# ESP32_WiFi.net
KiCad netlist of a schematic drawn in Altium Designer
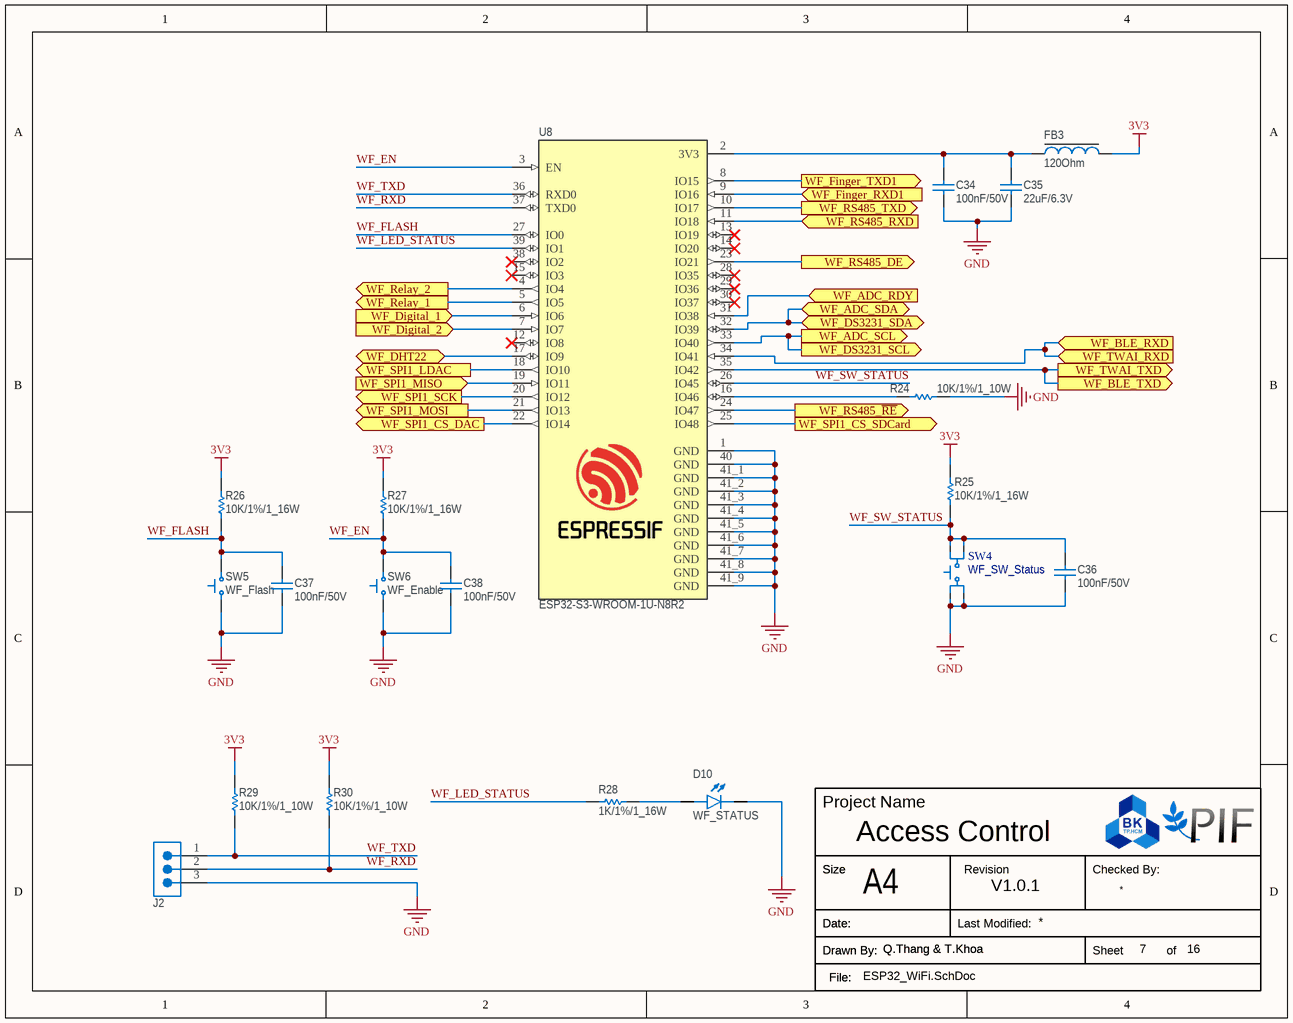
[diagram p0: ESP32_WiFi.SchDoc]

(export (version "E")
  (design (tool "Eeschema 10.0.6"))
  (components
    (comp (ref "C34")
      (value "100nF/50V")
      (footprint "CAP_0805")
      (description "CAP, size 0805, 100nF, 50V")
      (fields (field (name "SUPPLY PART NUMBER") "Tụ Gốm 0805 100nF (0.1uF) 50V"))
      (libsource (lib "BluetoothTracking") (part "Ceramic_Cap_100nF_50V_0805"))
    )
    (comp (ref "C35")
      (value "22uF/6.3V")
      (footprint "CAP_0805")
      (description "CAP, size 0805, 22uF, 6.3V")
      (fields (field (name "SUPPLY PART NUMBER") "Tụ Gốm 0805 22uF 6.3V"))
      (libsource (lib "BluetoothTracking") (part "Ceramic_Cap_22uF_6.3V_0805"))
    )
    (comp (ref "C36")
      (value "100nF/50V")
      (footprint "CAP_0402")
      (description "CAP, size 0402, 100nF, 50V")
      (fields (field (name "SUPPLY PART NUMBER") "Tụ Gốm 0402 100nF (0.1uF) 50V"))
      (libsource (lib "BluetoothTracking") (part "Ceramic_Cap_100nF_50V_0402"))
    )
    (comp (ref "C37")
      (value "100nF/50V")
      (footprint "CAP_0402")
      (description "CAP, size 0402, 100nF, 50V")
      (fields (field (name "SUPPLY PART NUMBER") "Tụ Gốm 0402 100nF (0.1uF) 50V"))
      (libsource (lib "BluetoothTracking") (part "Ceramic_Cap_100nF_50V_0402"))
    )
    (comp (ref "C38")
      (value "100nF/50V")
      (footprint "CAP_0402")
      (description "CAP, size 0402, 100nF, 50V")
      (fields (field (name "SUPPLY PART NUMBER") "Tụ Gốm 0402 100nF (0.1uF) 50V"))
      (libsource (lib "BluetoothTracking") (part "Ceramic_Cap_100nF_50V_0402"))
    )
    (comp (ref "D10")
      (value "WF_STATUS")
      (footprint "LED_0603Y")
      (description "LED Yellow 0603")
      (fields (field (name "SUPPLY PART NUMBER") "LED Vàng 0603 Dán SMD Trong Suốt Harvatek"))
      (libsource (lib "BluetoothTracking") (part "LED_Yellow_0603"))
    )
    (comp (ref "FB3")
      (value "120Ohm")
      (footprint "Ferrite_Bead_0805")
      (description "Ferrite Bead, size 0805, 120Ohm, 2A")
      (fields (field (name "SUPPLY PART NUMBER") "CBW201209U121T Ferrite Beads 2A 120 Ohm 0805"))
      (libsource (lib "BluetoothTracking") (part "Ferrite_Bead_120Ohm_2A_0805"))
    )
    (comp (ref "J2")
      (value "2.54mm_2P")
      (footprint "Header_2.54mm_3P")
      (description "Hàng Rào Đực Đơn 2.54mm 40 Chân 1 Hàng Cao 11.2mm Xuyên Lỗ")
      (libsource (lib "BluetoothTracking") (part "Header_2.54mm_3P"))
    )
    (comp (ref "R24")
      (value "10K/1%/1_10W")
      (footprint "Resistor_0603")
      (description "Resistor 0603 10KOhm 1% 1_10W")
      (fields (field (name "SUPPLY PART NUMBER") "Điện Trở 10 KOhm 0603 1%"))
      (libsource (lib "BluetoothTracking") (part "Res_10K_0603_1%"))
    )
    (comp (ref "R25")
      (value "10K/1%/1_16W")
      (footprint "RESISTOR_0402")
      (description "Resistor 0402 10KOhm 1% 1_16W")
      (fields (field (name "SUPPLY PART NUMBER") "Điện Trở 10 KOhm 0402 1%"))
      (libsource (lib "BluetoothTracking") (part "Res_10K_0402_1%"))
    )
    (comp (ref "R26")
      (value "10K/1%/1_16W")
      (footprint "RESISTOR_0402")
      (description "Resistor 0402 10KOhm 1% 1_16W")
      (fields (field (name "SUPPLY PART NUMBER") "Điện Trở 10 KOhm 0402 1%"))
      (libsource (lib "BluetoothTracking") (part "Res_10K_0402_1%"))
    )
    (comp (ref "R27")
      (value "10K/1%/1_16W")
      (footprint "RESISTOR_0402")
      (description "Resistor 0402 10KOhm 1% 1_16W")
      (fields (field (name "SUPPLY PART NUMBER") "Điện Trở 10 KOhm 0402 1%"))
      (libsource (lib "BluetoothTracking") (part "Res_10K_0402_1%"))
    )
    (comp (ref "R28")
      (value "1K/1%/1_16W")
      (footprint "RESISTOR_0402")
      (description "Resistor 0402 1KOhm 1% 1_16W")
      (fields (field (name "SUPPLY PART NUMBER") "Điện Trở 1 KOhm 0402 1%"))
      (libsource (lib "BluetoothTracking") (part "Res_1K_0402_1%"))
    )
    (comp (ref "R29")
      (value "10K/1%/1_10W")
      (footprint "Resistor_0603")
      (description "Resistor 0603 10KOhm 1% 1_10W")
      (fields (field (name "SUPPLY PART NUMBER") "Điện Trở 10 KOhm 0603 1%"))
      (libsource (lib "BluetoothTracking") (part "Res_10K_0603_1%"))
    )
    (comp (ref "R30")
      (value "10K/1%/1_10W")
      (footprint "Resistor_0603")
      (description "Resistor 0603 10KOhm 1% 1_10W")
      (fields (field (name "SUPPLY PART NUMBER") "Điện Trở 10 KOhm 0603 1%"))
      (libsource (lib "BluetoothTracking") (part "Res_10K_0603_1%"))
    )
    (comp (ref "SW4")
      (value "WF_SW_Status")
      (footprint "Button_4.5x4.7mm_SMD_4P")
      (fields (field (name "SUPPLY PART NUMBER") "Nút Nhấn Rùa 4.5x4.7mm Cao 1.65mm 4 Chân SMD"))
      (libsource (lib "BluetoothTracking") (part "Button_SMD_4.5x4.7mm_4P"))
    )
    (comp (ref "SW5")
      (value "WF_Flash")
      (footprint "Button_3x4mm_SMD_2P")
      (fields (field (name "SUPPLY PART NUMBER") "Nút Nhấn 3x4mm Cao 2.5mm 2 Chân SMD"))
      (libsource (lib "BluetoothTracking") (part "Button_SMD_3x4mm_2P"))
    )
    (comp (ref "SW6")
      (value "WF_Enable")
      (footprint "Button_3x4mm_SMD_2P")
      (fields (field (name "SUPPLY PART NUMBER") "Nút Nhấn 3x4mm Cao 2.5mm 2 Chân SMD"))
      (libsource (lib "BluetoothTracking") (part "Button_SMD_3x4mm_2P"))
    )
    (comp (ref "U8")
      (value "ESP32-S3-WROOM-1U-N8R2")
      (footprint "XCVR_ESP32-S3-WROOM-1U-N16R8")
      (fields
        (field (name "SUPPLY PART NUMBER") "ESP32-S3-WROOM-1U-N8R2 Module WiFi Bluetooth 8MB Flash, 2MB SRAM 2.4GHz")
      )
      (libsource (lib "BluetoothTracking") (part "ESP32-S3-WROOM-1U-N8R2"))
    )
  )
  (nets
    (net (code "1") (name "/WF_ADC_RDY") (class "Default")
      (node (ref "U8") (pin "31") (pinfunction "IO38_31") (pintype "input"))
    )
    (net (code "2") (name "/WF_ADC_SCL") (class "Default")
      (node (ref "U8") (pin "33") (pinfunction "IO40_33") (pintype "output"))
    )
    (net (code "3") (name "/WF_ADC_SDA") (class "Default")
      (node (ref "U8") (pin "32") (pinfunction "IO39_32") (pintype "bidirectional"))
    )
    (net (code "4") (name "/WF_BLE_RXD") (class "Default")
      (node (ref "U8") (pin "34") (pinfunction "IO41_34") (pintype "input"))
    )
    (net (code "5") (name "/WF_BLE_TXD") (class "Default")
      (node (ref "U8") (pin "35") (pinfunction "IO42_35") (pintype "output"))
    )
    (net (code "6") (name "/WF_DHT22") (class "Default")
      (node (ref "U8") (pin "17") (pinfunction "IO9_17") (pintype "bidirectional"))
    )
    (net (code "7") (name "/WF_Digital_1") (class "Default")
      (node (ref "U8") (pin "6") (pinfunction "IO6_6") (pintype "input"))
    )
    (net (code "8") (name "/WF_Digital_2") (class "Default")
      (node (ref "U8") (pin "7") (pinfunction "IO7_7") (pintype "input"))
    )
    (net (code "9") (name "/WF_EN") (class "Default")
      (node (ref "C38") (pin "2") (pinfunction "2_2") (pintype "passive"))
      (node (ref "R27") (pin "1") (pinfunction "1_1") (pintype "passive"))
      (node (ref "SW6") (pin "2") (pinfunction "2_2") (pintype "passive"))
      (node (ref "U8") (pin "3") (pinfunction "EN_3") (pintype "input"))
    )
    (net (code "10") (name "/WF_FLASH") (class "Default")
      (node (ref "C37") (pin "2") (pinfunction "2_2") (pintype "passive"))
      (node (ref "R26") (pin "1") (pinfunction "1_1") (pintype "passive"))
      (node (ref "SW5") (pin "2") (pinfunction "2_2") (pintype "passive"))
      (node (ref "U8") (pin "27") (pinfunction "IO0_27") (pintype "bidirectional"))
    )
    (net (code "11") (name "/WF_Finger_RXD1") (class "Default")
      (node (ref "U8") (pin "9") (pinfunction "IO16_9") (pintype "input"))
    )
    (net (code "12") (name "/WF_Finger_TXD1") (class "Default")
      (node (ref "U8") (pin "8") (pinfunction "IO15_8") (pintype "output"))
    )
    (net (code "13") (name "/WF_LED_STATUS") (class "Default")
      (node (ref "R28") (pin "1") (pinfunction "1_1") (pintype "passive"))
      (node (ref "U8") (pin "39") (pinfunction "IO1_39") (pintype "bidirectional"))
    )
    (net (code "14") (name "/WF_RS485_DE") (class "Default")
      (node (ref "U8") (pin "23") (pinfunction "IO21_23") (pintype "output"))
    )
    (net (code "15") (name "/WF_RS485_RXD") (class "Default")
      (node (ref "U8") (pin "11") (pinfunction "IO18_11") (pintype "input"))
    )
    (net (code "16") (name "/WF_RS485_TXD") (class "Default")
      (node (ref "U8") (pin "10") (pinfunction "IO17_10") (pintype "output"))
    )
    (net (code "17") (name "/WF_RS485_~{RE}") (class "Default")
      (node (ref "U8") (pin "24") (pinfunction "IO47_24") (pintype "output"))
    )
    (net (code "18") (name "/WF_RXD") (class "Default")
      (node (ref "J2") (pin "2") (pinfunction "2_2") (pintype "passive"))
      (node (ref "R30") (pin "1") (pinfunction "1_1") (pintype "passive"))
      (node (ref "U8") (pin "37") (pinfunction "TXD0_37") (pintype "bidirectional"))
    )
    (net (code "19") (name "/WF_Relay_1") (class "Default")
      (node (ref "U8") (pin "5") (pinfunction "IO5_5") (pintype "output"))
    )
    (net (code "20") (name "/WF_Relay_2") (class "Default")
      (node (ref "U8") (pin "4") (pinfunction "IO4_4") (pintype "output"))
    )
    (net (code "21") (name "/WF_SPI1_CS_DAC") (class "Default")
      (node (ref "U8") (pin "22") (pinfunction "IO14_22") (pintype "output"))
    )
    (net (code "22") (name "/WF_SPI1_CS_SDCard") (class "Default")
      (node (ref "U8") (pin "25") (pinfunction "IO48_25") (pintype "output"))
    )
    (net (code "23") (name "/WF_SPI1_LDAC") (class "Default")
      (node (ref "U8") (pin "18") (pinfunction "IO10_18") (pintype "output"))
    )
    (net (code "24") (name "/WF_SPI1_MISO") (class "Default")
      (node (ref "U8") (pin "19") (pinfunction "IO11_19") (pintype "input"))
    )
    (net (code "25") (name "/WF_SPI1_MOSI") (class "Default")
      (node (ref "U8") (pin "21") (pinfunction "IO13_21") (pintype "output"))
    )
    (net (code "26") (name "/WF_SPI1_SCK") (class "Default")
      (node (ref "U8") (pin "20") (pinfunction "IO12_20") (pintype "output"))
    )
    (net (code "27") (name "/WF_SW_STATUS") (class "Default")
      (node (ref "C36") (pin "2") (pinfunction "2_2") (pintype "passive"))
      (node (ref "R25") (pin "1") (pinfunction "1_1") (pintype "passive"))
      (node (ref "SW4") (pin "1") (pinfunction "1_1") (pintype "passive"))
      (node (ref "SW4") (pin "2") (pinfunction "2_2") (pintype "passive"))
      (node (ref "U8") (pin "26") (pinfunction "IO45_26") (pintype "bidirectional"))
    )
    (net (code "28") (name "/WF_TXD") (class "Default")
      (node (ref "J2") (pin "1") (pinfunction "1_1") (pintype "passive"))
      (node (ref "R29") (pin "1") (pinfunction "1_1") (pintype "passive"))
      (node (ref "U8") (pin "36") (pinfunction "RXD0_36") (pintype "bidirectional"))
    )
    (net (code "29") (name "3V3") (class "Default")
      (node (ref "FB3") (pin "2") (pinfunction "2_2") (pintype "passive"))
      (node (ref "R25") (pin "2") (pinfunction "2_2") (pintype "passive"))
      (node (ref "R26") (pin "2") (pinfunction "2_2") (pintype "passive"))
      (node (ref "R27") (pin "2") (pinfunction "2_2") (pintype "passive"))
      (node (ref "R29") (pin "2") (pinfunction "2_2") (pintype "passive"))
      (node (ref "R30") (pin "2") (pinfunction "2_2") (pintype "passive"))
    )
    (net (code "30") (name "GND") (class "Default")
      (node (ref "C34") (pin "1") (pinfunction "1_1") (pintype "passive"))
      (node (ref "C35") (pin "1") (pinfunction "1_1") (pintype "passive"))
      (node (ref "C36") (pin "1") (pinfunction "1_1") (pintype "passive"))
      (node (ref "C37") (pin "1") (pinfunction "1_1") (pintype "passive"))
      (node (ref "C38") (pin "1") (pinfunction "1_1") (pintype "passive"))
      (node (ref "D10") (pin "C") (pinfunction "C_C") (pintype "passive"))
      (node (ref "J2") (pin "3") (pinfunction "3_3") (pintype "passive"))
      (node (ref "R24") (pin "1") (pinfunction "1_1") (pintype "passive"))
      (node (ref "SW4") (pin "3") (pinfunction "3_3") (pintype "passive"))
      (node (ref "SW4") (pin "4") (pinfunction "4_4") (pintype "passive"))
      (node (ref "SW5") (pin "1") (pinfunction "1_1") (pintype "passive"))
      (node (ref "SW6") (pin "1") (pinfunction "1_1") (pintype "passive"))
      (node (ref "U8") (pin "1") (pinfunction "GND_1") (pintype "power_in"))
      (node (ref "U8") (pin "40") (pinfunction "GND_40") (pintype "power_in"))
      (node (ref "U8") (pin "41_1") (pinfunction "GND_41_1") (pintype "power_in"))
      (node (ref "U8") (pin "41_2") (pinfunction "GND_41_2") (pintype "power_in"))
      (node (ref "U8") (pin "41_3") (pinfunction "GND_41_3") (pintype "power_in"))
      (node (ref "U8") (pin "41_4") (pinfunction "GND_41_4") (pintype "power_in"))
      (node (ref "U8") (pin "41_5") (pinfunction "GND_41_5") (pintype "power_in"))
      (node (ref "U8") (pin "41_6") (pinfunction "GND_41_6") (pintype "power_in"))
      (node (ref "U8") (pin "41_7") (pinfunction "GND_41_7") (pintype "power_in"))
      (node (ref "U8") (pin "41_8") (pinfunction "GND_41_8") (pintype "power_in"))
      (node (ref "U8") (pin "41_9") (pinfunction "GND_41_9") (pintype "power_in"))
    )
    (net (code "31") (name "Net-(D10-PadA)") (class "Default")
      (node (ref "D10") (pin "A") (pinfunction "A_A") (pintype "passive"))
      (node (ref "R28") (pin "2") (pinfunction "2_2") (pintype "passive"))
    )
    (net (code "32") (name "Net-(U8-3V3)") (class "Default")
      (node (ref "C34") (pin "2") (pinfunction "2_2") (pintype "passive"))
      (node (ref "C35") (pin "2") (pinfunction "2_2") (pintype "passive"))
      (node (ref "FB3") (pin "1") (pinfunction "1_1") (pintype "passive"))
      (node (ref "U8") (pin "2") (pinfunction "3V3_2") (pintype "power_in"))
    )
    (net (code "33") (name "Net-(U8-IO46)") (class "Default")
      (node (ref "R24") (pin "2") (pinfunction "2_2") (pintype "passive"))
      (node (ref "U8") (pin "16") (pinfunction "IO46_16") (pintype "bidirectional"))
    )
    (net (code "34") (name "unconnected-(U8-IO2-Pad38)") (class "Default")
      (node (ref "U8") (pin "38") (pinfunction "IO2_38") (pintype "bidirectional+no_connect"))
    )
    (net (code "35") (name "unconnected-(U8-IO3-Pad15)") (class "Default")
      (node (ref "U8") (pin "15") (pinfunction "IO3_15") (pintype "bidirectional+no_connect"))
    )
    (net (code "36") (name "unconnected-(U8-IO8-Pad12)") (class "Default")
      (node (ref "U8") (pin "12") (pinfunction "IO8_12") (pintype "bidirectional+no_connect"))
    )
    (net (code "37") (name "unconnected-(U8-IO19-Pad13)") (class "Default")
      (node (ref "U8") (pin "13") (pinfunction "IO19_13") (pintype "bidirectional+no_connect"))
    )
    (net (code "38") (name "unconnected-(U8-IO20-Pad14)") (class "Default")
      (node (ref "U8") (pin "14") (pinfunction "IO20_14") (pintype "bidirectional+no_connect"))
    )
    (net (code "39") (name "unconnected-(U8-IO35-Pad28)") (class "Default")
      (node (ref "U8") (pin "28") (pinfunction "IO35_28") (pintype "bidirectional+no_connect"))
    )
    (net (code "40") (name "unconnected-(U8-IO36-Pad29)") (class "Default")
      (node (ref "U8") (pin "29") (pinfunction "IO36_29") (pintype "bidirectional+no_connect"))
    )
    (net (code "41") (name "unconnected-(U8-IO37-Pad30)") (class "Default")
      (node (ref "U8") (pin "30") (pinfunction "IO37_30") (pintype "bidirectional+no_connect"))
    )
  )
)
